# ethernet_ipphone_sch.net
KiCad netlist of a schematic drawn in Altium Designer
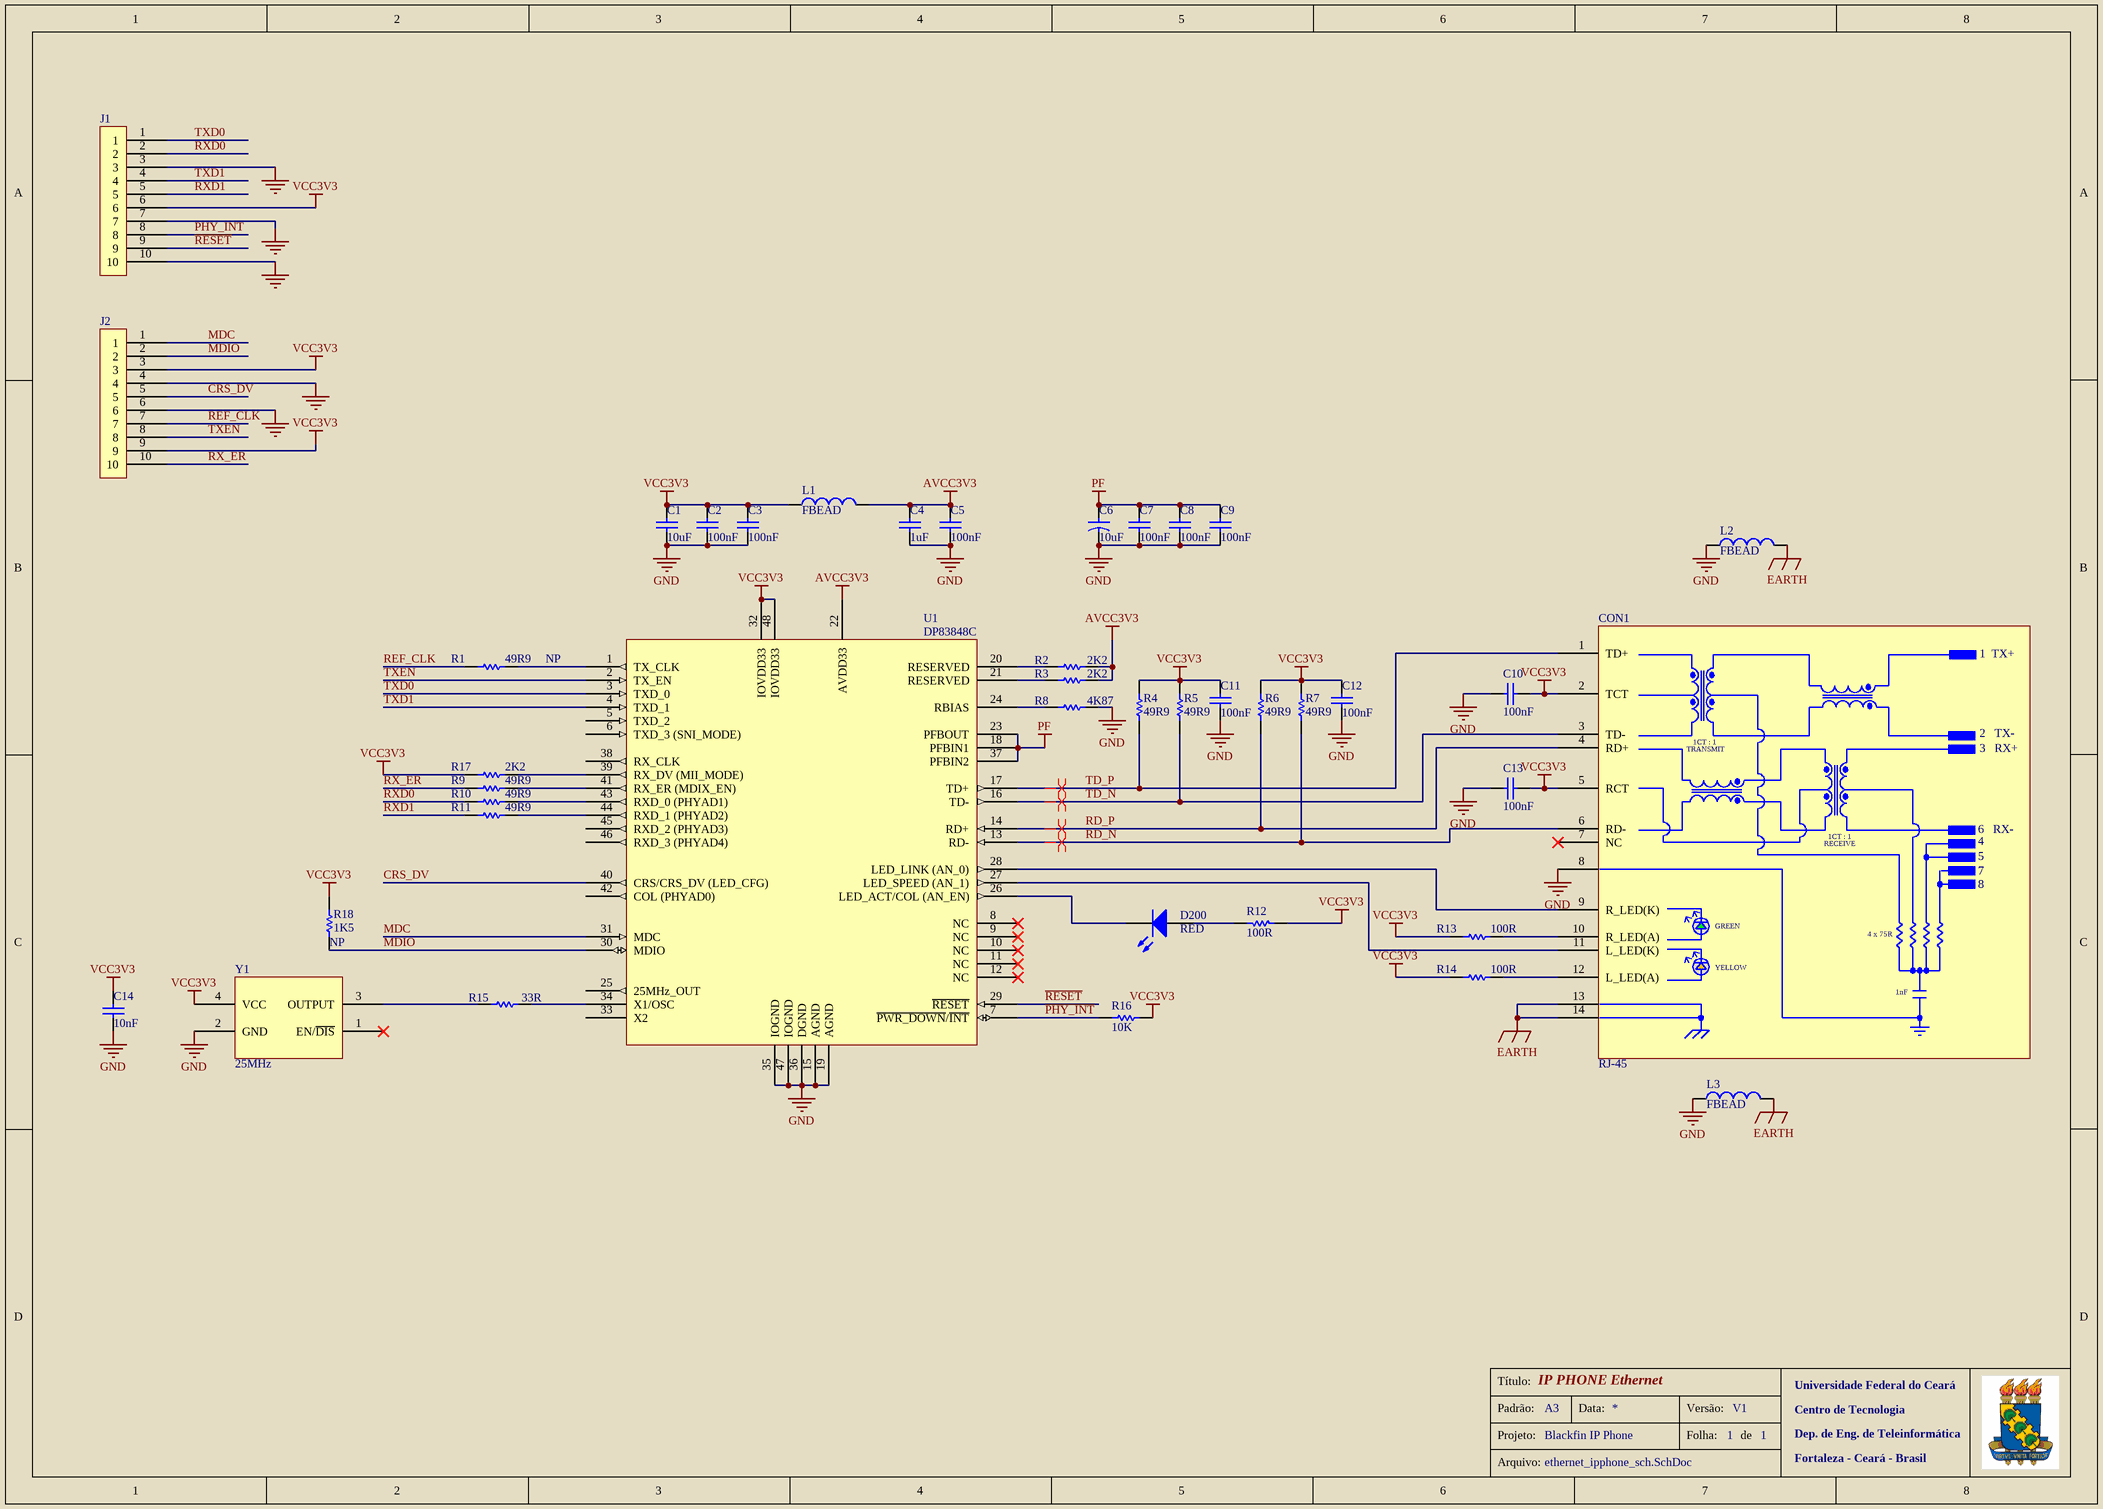
[diagram p0: ethernet_ipphone_sch.SchDoc]

(export (version "E")
  (design (tool "Eeschema 10.0.6"))
  (components
    (comp (ref "C1")
      (value "10uF")
      (footprint "ip_phone:CC2012-0805")
      (description "Capacitor SMD/SMT 0603 10uF 6.3volts X5R 20%")
      (fields (field (name "EVENDORPART#") "810-C2012Y5V1A106Z") (field (name "MANUFACTURER") "TDK"))
      (libsource (lib "ip_phone") (part "Capacitor"))
    )
    (comp (ref "C2")
      (value "100nF")
      (footprint "ip_phone:CC1005-0402")
      (description "MLCC - SMD/SMT 0.1UF 16V 10% 0402")
      (fields (field (name "EVENDORPART#") "810-C1005X7R1C104K") (field (name "MANUFACTURER") "TDK"))
      (libsource (lib "ip_phone") (part "Capacitor"))
    )
    (comp (ref "C3")
      (value "100nF")
      (footprint "ip_phone:CC1005-0402")
      (description "MLCC - SMD/SMT 0.1UF 16V 10% 0402")
      (fields (field (name "EVENDORPART#") "810-C1005X7R1C104K") (field (name "MANUFACTURER") "TDK"))
      (libsource (lib "ip_phone") (part "Capacitor"))
    )
    (comp (ref "C4")
      (value "1uF")
      (footprint "ip_phone:CC1608-0603")
      (description "Capacitor")
      (libsource (lib "ip_phone") (part "Capacitor"))
    )
    (comp (ref "C5")
      (value "100nF")
      (footprint "ip_phone:CC1005-0402")
      (description "MLCC - SMD/SMT 0.1UF 16V 10% 0402")
      (fields (field (name "EVENDORPART#") "810-C1005X7R1C104K") (field (name "MANUFACTURER") "TDK"))
      (libsource (lib "ip_phone") (part "Capacitor"))
    )
    (comp (ref "C6")
      (value "10uF")
      (footprint "ip_phone:C_Case_A")
      (description "Capacitor Tantalum")
      (libsource (lib "ip_phone") (part "Capacitor_Tan"))
    )
    (comp (ref "C7")
      (value "100nF")
      (footprint "ip_phone:CC1005-0402")
      (description "MLCC - SMD/SMT 0.1UF 16V 10% 0402")
      (fields (field (name "EVENDORPART#") "810-C1005X7R1C104K") (field (name "MANUFACTURER") "TDK"))
      (libsource (lib "ip_phone") (part "Capacitor"))
    )
    (comp (ref "C8")
      (value "100nF")
      (footprint "ip_phone:CC1005-0402")
      (description "MLCC - SMD/SMT 0.1UF 16V 10% 0402")
      (fields (field (name "EVENDORPART#") "810-C1005X7R1C104K") (field (name "MANUFACTURER") "TDK"))
      (libsource (lib "ip_phone") (part "Capacitor"))
    )
    (comp (ref "C9")
      (value "100nF")
      (footprint "ip_phone:CC1005-0402")
      (description "MLCC - SMD/SMT 0.1UF 16V 10% 0402")
      (fields (field (name "EVENDORPART#") "810-C1005X7R1C104K") (field (name "MANUFACTURER") "TDK"))
      (libsource (lib "ip_phone") (part "Capacitor"))
    )
    (comp (ref "C10")
      (value "100nF")
      (footprint "ip_phone:CC1005-0402")
      (description "MLCC - SMD/SMT 0.1UF 16V 10% 0402")
      (fields (field (name "EVENDORPART#") "810-C1005X7R1C104K") (field (name "MANUFACTURER") "TDK"))
      (libsource (lib "ip_phone") (part "Capacitor"))
    )
    (comp (ref "C11")
      (value "100nF")
      (footprint "ip_phone:CC1005-0402")
      (description "MLCC - SMD/SMT 0.1UF 16V 10% 0402")
      (fields (field (name "EVENDORPART#") "810-C1005X7R1C104K") (field (name "MANUFACTURER") "TDK"))
      (libsource (lib "ip_phone") (part "Capacitor"))
    )
    (comp (ref "C12")
      (value "100nF")
      (footprint "ip_phone:CC1005-0402")
      (description "MLCC - SMD/SMT 0.1UF 16V 10% 0402")
      (fields (field (name "EVENDORPART#") "810-C1005X7R1C104K") (field (name "MANUFACTURER") "TDK"))
      (libsource (lib "ip_phone") (part "Capacitor"))
    )
    (comp (ref "C13")
      (value "100nF")
      (footprint "ip_phone:CC1005-0402")
      (description "MLCC - SMD/SMT 0.1UF 16V 10% 0402")
      (fields (field (name "EVENDORPART#") "810-C1005X7R1C104K") (field (name "MANUFACTURER") "TDK"))
      (libsource (lib "ip_phone") (part "Capacitor"))
    )
    (comp (ref "C14")
      (value "10nF")
      (footprint "ip_phone:CC1005-0402")
      (description "Capacitor SMD/SMT 0402 0.01uF 16volts X7R 10%")
      (fields (field (name "EVENDORPART#") "810-C1005X7R1C103K") (field (name "MANUFACTURER") "TDK"))
      (libsource (lib "ip_phone") (part "Capacitor"))
    )
    (comp (ref "CON1")
      (value "RJ-45")
      (footprint "ip_phone:RJ-45")
      (description "Ethernet & Telecom Connectors 1X1 RJ45 JACK")
      (fields (field (name "EVENDORPART#") "673-J1012F01C") (field (name "PART#") "J1012F01C"))
      (libsource (lib "ip_phone") (part "RJ-45"))
    )
    (comp (ref "D200")
      (value "RED")
      (footprint "ip_phone:LED_0603")
      (description "LED")
      (fields (field (name "PART#") "APT1608SURCK") (field (name "MANUFACTURER") "Kingbright"))
      (libsource (lib "ip_phone") (part "LED"))
    )
    (comp (ref "J1")
      (value "CONN HEADER")
      (footprint "ip_phone:CONECTOR_10_PIN")
      (description "CONN HEADER .050\" 10POS PCB GOLD")
      (fields
        (field (name "EVENDORPART#") "S9014E-10-ND")
        (field (name "MANUFACTURER") "Sullins Connector Solutions")
      )
      (libsource (lib "ip_phone") (part "Conector 10pin"))
    )
    (comp (ref "J2")
      (value "CONN HEADER")
      (footprint "ip_phone:CONECTOR_10_PIN")
      (description "CONN HEADER .050\" 10POS PCB GOLD")
      (fields
        (field (name "EVENDORPART#") "S9014E-10-ND")
        (field (name "MANUFACTURER") "Sullins Connector Solutions")
      )
      (libsource (lib "ip_phone") (part "Conector 10pin"))
    )
    (comp (ref "L1")
      (value "FBEAD")
      (footprint "ip_phone:INDUTOR_0603")
      (description "Inductor")
      (libsource (lib "ip_phone") (part "Inductor"))
    )
    (comp (ref "L2")
      (value "FBEAD")
      (footprint "ip_phone:INDUTOR_0603")
      (description "Inductor")
      (libsource (lib "ip_phone") (part "Inductor"))
    )
    (comp (ref "L3")
      (value "FBEAD")
      (footprint "ip_phone:INDUTOR_0603")
      (description "Inductor")
      (libsource (lib "ip_phone") (part "Inductor"))
    )
    (comp (ref "R1")
      (value "49R9")
      (footprint "ip_phone:CR1005-0402_NP")
      (description "Thick Film Resistors - SMD 1/16watt 49.9ohms 1% 0402")
      (fields
        (field (name "EVENDORPART#") "71-CRCW0402-49.9-E3")
        (field (name "MANUFACTURER") "Vishay/Dale")
        (field (name "NP") "NP")
      )
      (libsource (lib "ip_phone") (part "Resistor"))
    )
    (comp (ref "R2")
      (value "2K2")
      (footprint "ip_phone:CR1005-0402")
      (description "Thick Film Resistors SMD 0402 2K2 5%  1/16 W")
      (fields (field (name "EVENDORPART#") "311-2.2KJRCT-ND") (field (name "MANUFACTURER") "Yageo"))
      (libsource (lib "ip_phone") (part "Resistor"))
    )
    (comp (ref "R3")
      (value "2K2")
      (footprint "ip_phone:CR1005-0402")
      (description "Thick Film Resistors SMD 0402 2K2 5%  1/16 W")
      (fields (field (name "EVENDORPART#") "311-2.2KJRCT-ND") (field (name "MANUFACTURER") "Yageo"))
      (libsource (lib "ip_phone") (part "Resistor"))
    )
    (comp (ref "R4")
      (value "49R9")
      (footprint "ip_phone:CR1005-0402")
      (description "Thick Film Resistors - SMD 1/16watt 49.9ohms 1% 0402")
      (fields (field (name "EVENDORPART#") "71-CRCW0402-49.9-E3") (field (name "MANUFACTURER") "Vishay/Dale"))
      (libsource (lib "ip_phone") (part "Resistor"))
    )
    (comp (ref "R5")
      (value "49R9")
      (footprint "ip_phone:CR1005-0402")
      (description "Thick Film Resistors - SMD 1/16watt 49.9ohms 1% 0402")
      (fields (field (name "EVENDORPART#") "71-CRCW0402-49.9-E3") (field (name "MANUFACTURER") "Vishay/Dale"))
      (libsource (lib "ip_phone") (part "Resistor"))
    )
    (comp (ref "R6")
      (value "49R9")
      (footprint "ip_phone:CR1005-0402")
      (description "Thick Film Resistors - SMD 1/16watt 49.9ohms 1% 0402")
      (fields (field (name "EVENDORPART#") "71-CRCW0402-49.9-E3") (field (name "MANUFACTURER") "Vishay/Dale"))
      (libsource (lib "ip_phone") (part "Resistor"))
    )
    (comp (ref "R7")
      (value "49R9")
      (footprint "ip_phone:CR1005-0402")
      (description "Thick Film Resistors - SMD 1/16watt 49.9ohms 1% 0402")
      (fields (field (name "EVENDORPART#") "71-CRCW0402-49.9-E3") (field (name "MANUFACTURER") "Vishay/Dale"))
      (libsource (lib "ip_phone") (part "Resistor"))
    )
    (comp (ref "R8")
      (value "4K87")
      (footprint "ip_phone:CR1608-0603")
      (libsource (lib "ip_phone") (part "Resistor"))
    )
    (comp (ref "R9")
      (value "49R9")
      (footprint "ip_phone:CR1005-0402")
      (description "Thick Film Resistors - SMD 1/16watt 49.9ohms 1% 0402")
      (fields (field (name "EVENDORPART#") "71-CRCW0402-49.9-E3") (field (name "MANUFACTURER") "Vishay/Dale"))
      (libsource (lib "ip_phone") (part "Resistor"))
    )
    (comp (ref "R10")
      (value "49R9")
      (footprint "ip_phone:CR1005-0402")
      (description "Thick Film Resistors - SMD 1/16watt 49.9ohms 1% 0402")
      (fields (field (name "EVENDORPART#") "71-CRCW0402-49.9-E3") (field (name "MANUFACTURER") "Vishay/Dale"))
      (libsource (lib "ip_phone") (part "Resistor"))
    )
    (comp (ref "R11")
      (value "49R9")
      (footprint "ip_phone:CR1005-0402")
      (description "Thick Film Resistors - SMD 1/16watt 49.9ohms 1% 0402")
      (fields (field (name "EVENDORPART#") "71-CRCW0402-49.9-E3") (field (name "MANUFACTURER") "Vishay/Dale"))
      (libsource (lib "ip_phone") (part "Resistor"))
    )
    (comp (ref "R12")
      (value "100R")
      (footprint "ip_phone:CR1608-0603")
      (description "Thick Film Resistors 1/16WATT 100R 0402")
      (fields (field (name "EVENDORPART#") "652-CR0603-JW-101GLF") (field (name "MANUFACTURER") "Bourns"))
      (libsource (lib "ip_phone") (part "Resistor"))
    )
    (comp (ref "R13")
      (value "100R")
      (footprint "ip_phone:CR1608-0603")
      (description "Thick Film Resistors 1/16WATT 100R 0402")
      (fields (field (name "EVENDORPART#") "652-CR0603-JW-101GLF") (field (name "MANUFACTURER") "Bourns"))
      (libsource (lib "ip_phone") (part "Resistor"))
    )
    (comp (ref "R14")
      (value "100R")
      (footprint "ip_phone:CR1608-0603")
      (description "Thick Film Resistors 1/16WATT 100R 0402")
      (fields (field (name "EVENDORPART#") "652-CR0603-JW-101GLF") (field (name "MANUFACTURER") "Bourns"))
      (libsource (lib "ip_phone") (part "Resistor"))
    )
    (comp (ref "R15")
      (value "33R")
      (footprint "ip_phone:CR1005-0402")
      (description "Thick Film Resistors SMD 0402 33R 5%  1/16 W")
      (fields (field (name "EVENDORPART#") "311-33JRCT-ND") (field (name "MANUFACTURER") "Yageo"))
      (libsource (lib "ip_phone") (part "Resistor"))
    )
    (comp (ref "R16")
      (value "10K")
      (footprint "ip_phone:CR1005-0402")
      (description "Thick Film Resistors SMD 0402 10K 5%  1/16 W")
      (fields (field (name "EVENDORPART#") "311-10KJRCT-ND") (field (name "MANUFACTURER") "Yageo"))
      (libsource (lib "ip_phone") (part "Resistor"))
    )
    (comp (ref "R17")
      (value "2K2")
      (footprint "ip_phone:CR1005-0402")
      (description "Thick Film Resistors SMD 0402 2K2 5%  1/16 W")
      (fields (field (name "EVENDORPART#") "311-2.2KJRCT-ND") (field (name "MANUFACTURER") "Yageo"))
      (libsource (lib "ip_phone") (part "Resistor"))
    )
    (comp (ref "R18")
      (value "1K5")
      (footprint "ip_phone:CR1608-0603")
      (description "Thick Film Resistors 1.5KOHM 5% 1/10W")
      (fields
        (field (name "EVENDORPART#") "52-CR0603-JW-152GLF")
        (field (name "MANUFACTURER") "Bourns")
        (field (name "NP") "NP")
      )
      (libsource (lib "ip_phone") (part "Resistor"))
    )
    (comp (ref "U1")
      (value "DP83848C")
      (footprint "ip_phone:LQFP48")
      (description "IC TXRX ETHERNET PHYTER 48-LQFP")
      (fields (field (name "MANUFACTURER") "National Semiconductor") (field (name "PART#") "DP83848CVV/NOPB"))
      (libsource (lib "ip_phone") (part "DP83848C"))
    )
    (comp (ref "Y1")
      (value "25MHz")
      (footprint "ip_phone:OSC_25MHz_PHY")
      (description "Standard Clock Oscillators 3.3V 25MHZ")
      (fields (field (name "EVENDORPART#") "815-ASV-25-EJ-T") (field (name "PART#") "ASV-25.000MHZ-EJ-T"))
      (libsource (lib "ip_phone") (part "Oscillator_25MHz_Phy"))
    )
  )
  (nets
    (net (code "1") (name "/CRS_DV") (class "Default")
      (node (ref "J2") (pin "5") (pinfunction "5_5") (pintype "passive"))
      (node (ref "U1") (pin "40") (pinfunction "CRS/CRS_DV_(LED_CFG)_40") (pintype "output"))
    )
    (net (code "2") (name "/MDC") (class "Default")
      (node (ref "J2") (pin "1") (pinfunction "1_1") (pintype "passive"))
      (node (ref "U1") (pin "31") (pinfunction "MDC_31") (pintype "input"))
    )
    (net (code "3") (name "/MDIO") (class "Default")
      (node (ref "J2") (pin "2") (pinfunction "2_2") (pintype "passive"))
      (node (ref "R18") (pin "2") (pinfunction "2_2") (pintype "passive"))
      (node (ref "U1") (pin "30") (pinfunction "MDIO_30") (pintype "bidirectional"))
    )
    (net (code "4") (name "/RD_N") (class "Default")
      (node (ref "CON1") (pin "6") (pinfunction "RD-_6") (pintype "passive"))
      (node (ref "R7") (pin "1") (pinfunction "1_1") (pintype "passive"))
      (node (ref "U1") (pin "13") (pinfunction "RD-_13") (pintype "input"))
    )
    (net (code "5") (name "/RD_P") (class "Default")
      (node (ref "CON1") (pin "4") (pinfunction "RD+_4") (pintype "passive"))
      (node (ref "R6") (pin "1") (pinfunction "1_1") (pintype "passive"))
      (node (ref "U1") (pin "14") (pinfunction "RD+_14") (pintype "input"))
    )
    (net (code "6") (name "/REF_CLK") (class "Default")
      (node (ref "J2") (pin "7") (pinfunction "7_7") (pintype "passive"))
      (node (ref "R1") (pin "1") (pinfunction "1_1") (pintype "passive"))
    )
    (net (code "7") (name "/RXD0") (class "Default")
      (node (ref "J1") (pin "2") (pinfunction "2_2") (pintype "passive"))
      (node (ref "R10") (pin "1") (pinfunction "1_1") (pintype "passive"))
    )
    (net (code "8") (name "/RXD1") (class "Default")
      (node (ref "J1") (pin "5") (pinfunction "5_5") (pintype "passive"))
      (node (ref "R11") (pin "1") (pinfunction "1_1") (pintype "passive"))
    )
    (net (code "9") (name "/RX_ER") (class "Default")
      (node (ref "J2") (pin "10") (pinfunction "10_10") (pintype "passive"))
      (node (ref "R9") (pin "1") (pinfunction "1_1") (pintype "passive"))
    )
    (net (code "10") (name "/TD_N") (class "Default")
      (node (ref "CON1") (pin "3") (pinfunction "TD-_3") (pintype "passive"))
      (node (ref "R5") (pin "1") (pinfunction "1_1") (pintype "passive"))
      (node (ref "U1") (pin "16") (pinfunction "TD-_16") (pintype "output"))
    )
    (net (code "11") (name "/TD_P") (class "Default")
      (node (ref "CON1") (pin "1") (pinfunction "TD+_1") (pintype "passive"))
      (node (ref "R4") (pin "1") (pinfunction "1_1") (pintype "passive"))
      (node (ref "U1") (pin "17") (pinfunction "TD+_17") (pintype "output"))
    )
    (net (code "12") (name "/TXD0") (class "Default")
      (node (ref "J1") (pin "1") (pinfunction "1_1") (pintype "passive"))
      (node (ref "U1") (pin "3") (pinfunction "TXD_0_3") (pintype "input"))
    )
    (net (code "13") (name "/TXD1") (class "Default")
      (node (ref "J1") (pin "4") (pinfunction "4_4") (pintype "passive"))
      (node (ref "U1") (pin "4") (pinfunction "TXD_1_4") (pintype "input"))
    )
    (net (code "14") (name "/TXEN") (class "Default")
      (node (ref "J2") (pin "8") (pinfunction "8_8") (pintype "passive"))
      (node (ref "U1") (pin "2") (pinfunction "TX_EN_2") (pintype "input"))
    )
    (net (code "15") (name "/~{PHY_INT}") (class "Default")
      (node (ref "J1") (pin "8") (pinfunction "8_8") (pintype "passive"))
      (node (ref "R16") (pin "2") (pinfunction "2_2") (pintype "passive"))
      (node (ref "U1") (pin "7") (pinfunction "~{PWR_DOWN}/~{INT}_7") (pintype "bidirectional"))
    )
    (net (code "16") (name "/~{RESET}") (class "Default")
      (node (ref "J1") (pin "9") (pinfunction "9_9") (pintype "passive"))
      (node (ref "U1") (pin "29") (pinfunction "~{RESET}_29") (pintype "input"))
    )
    (net (code "17") (name "AVCC3V3") (class "Default")
      (node (ref "C4") (pin "2") (pinfunction "2_2") (pintype "passive"))
      (node (ref "C5") (pin "2") (pinfunction "2_2") (pintype "passive"))
      (node (ref "L1") (pin "2") (pinfunction "2_2") (pintype "passive"))
      (node (ref "R2") (pin "2") (pinfunction "2_2") (pintype "passive"))
      (node (ref "R3") (pin "2") (pinfunction "2_2") (pintype "passive"))
      (node (ref "U1") (pin "22") (pinfunction "AVDD33_22") (pintype "power_in"))
    )
    (net (code "18") (name "EARTH") (class "Default")
      (node (ref "CON1") (pin "13") (pinfunction "GND_13") (pintype "passive"))
      (node (ref "CON1") (pin "14") (pinfunction "GND_14") (pintype "passive"))
      (node (ref "L2") (pin "2") (pinfunction "2_2") (pintype "passive"))
      (node (ref "L3") (pin "2") (pinfunction "2_2") (pintype "passive"))
    )
    (net (code "19") (name "GND") (class "Default")
      (node (ref "C1") (pin "1") (pinfunction "1_1") (pintype "passive"))
      (node (ref "C10") (pin "2") (pinfunction "2_2") (pintype "passive"))
      (node (ref "C11") (pin "1") (pinfunction "1_1") (pintype "passive"))
      (node (ref "C12") (pin "1") (pinfunction "1_1") (pintype "passive"))
      (node (ref "C13") (pin "2") (pinfunction "2_2") (pintype "passive"))
      (node (ref "C14") (pin "1") (pinfunction "1_1") (pintype "passive"))
      (node (ref "C2") (pin "1") (pinfunction "1_1") (pintype "passive"))
      (node (ref "C3") (pin "1") (pinfunction "1_1") (pintype "passive"))
      (node (ref "C4") (pin "1") (pinfunction "1_1") (pintype "passive"))
      (node (ref "C5") (pin "1") (pinfunction "1_1") (pintype "passive"))
      (node (ref "C6") (pin "2") (pinfunction "2_2") (pintype "passive"))
      (node (ref "C7") (pin "1") (pinfunction "1_1") (pintype "passive"))
      (node (ref "C8") (pin "1") (pinfunction "1_1") (pintype "passive"))
      (node (ref "C9") (pin "1") (pinfunction "1_1") (pintype "passive"))
      (node (ref "CON1") (pin "8") (pinfunction "GND_8") (pintype "passive"))
      (node (ref "J1") (pin "10") (pinfunction "10_10") (pintype "passive"))
      (node (ref "J1") (pin "3") (pinfunction "3_3") (pintype "passive"))
      (node (ref "J1") (pin "7") (pinfunction "7_7") (pintype "passive"))
      (node (ref "J2") (pin "4") (pinfunction "4_4") (pintype "passive"))
      (node (ref "J2") (pin "6") (pinfunction "6_6") (pintype "passive"))
      (node (ref "L2") (pin "1") (pinfunction "1_1") (pintype "passive"))
      (node (ref "L3") (pin "1") (pinfunction "1_1") (pintype "passive"))
      (node (ref "R8") (pin "2") (pinfunction "2_2") (pintype "passive"))
      (node (ref "U1") (pin "15") (pinfunction "AGND_15") (pintype "power_in"))
      (node (ref "U1") (pin "19") (pinfunction "AGND_19") (pintype "power_in"))
      (node (ref "U1") (pin "35") (pinfunction "IOGND_35") (pintype "power_in"))
      (node (ref "U1") (pin "36") (pinfunction "DGND_36") (pintype "power_in"))
      (node (ref "U1") (pin "47") (pinfunction "IOGND_47") (pintype "power_in"))
      (node (ref "Y1") (pin "2") (pinfunction "GND_2") (pintype "passive"))
    )
    (net (code "20") (name "Net-(CON1-L_LED(A))") (class "Default")
      (node (ref "CON1") (pin "12") (pinfunction "L_LED(A)_12") (pintype "passive"))
      (node (ref "R14") (pin "1") (pinfunction "1_1") (pintype "passive"))
    )
    (net (code "21") (name "Net-(CON1-L_LED(K))") (class "Default")
      (node (ref "CON1") (pin "11") (pinfunction "L_LED(K)_11") (pintype "passive"))
      (node (ref "U1") (pin "27") (pinfunction "LED_SPEED_(AN_1)_27") (pintype "output"))
    )
    (net (code "22") (name "Net-(CON1-R_LED(A))") (class "Default")
      (node (ref "CON1") (pin "10") (pinfunction "R_LED(A)_10") (pintype "passive"))
      (node (ref "R13") (pin "1") (pinfunction "1_1") (pintype "passive"))
    )
    (net (code "23") (name "Net-(CON1-R_LED(K))") (class "Default")
      (node (ref "CON1") (pin "9") (pinfunction "R_LED(K)_9") (pintype "passive"))
      (node (ref "U1") (pin "28") (pinfunction "LED_LINK_(AN_0)_28") (pintype "output"))
    )
    (net (code "24") (name "Net-(D200-A)") (class "Default")
      (node (ref "D200") (pin "1") (pinfunction "A_1") (pintype "passive"))
      (node (ref "R12") (pin "1") (pinfunction "1_1") (pintype "passive"))
    )
    (net (code "25") (name "Net-(D200-K)") (class "Default")
      (node (ref "D200") (pin "2") (pinfunction "K_2") (pintype "passive"))
      (node (ref "U1") (pin "26") (pinfunction "LED_ACT/COL_(AN_EN)_26") (pintype "output"))
    )
    (net (code "26") (name "Net-(R2-Pad1)") (class "Default")
      (node (ref "R2") (pin "1") (pinfunction "1_1") (pintype "passive"))
      (node (ref "U1") (pin "20") (pinfunction "RESERVED_20") (pintype "passive"))
    )
    (net (code "27") (name "Net-(R3-Pad1)") (class "Default")
      (node (ref "R3") (pin "1") (pinfunction "1_1") (pintype "passive"))
      (node (ref "U1") (pin "21") (pinfunction "RESERVED_21") (pintype "passive"))
    )
    (net (code "28") (name "Net-(U1-RBIAS)") (class "Default")
      (node (ref "R8") (pin "1") (pinfunction "1_1") (pintype "passive"))
      (node (ref "U1") (pin "24") (pinfunction "RBIAS_24") (pintype "passive"))
    )
    (net (code "29") (name "Net-(U1-RXD_0_(PHYAD1))") (class "Default")
      (node (ref "R10") (pin "2") (pinfunction "2_2") (pintype "passive"))
      (node (ref "U1") (pin "43") (pinfunction "RXD_0_(PHYAD1)_43") (pintype "output"))
    )
    (net (code "30") (name "Net-(U1-RXD_1_(PHYAD2))") (class "Default")
      (node (ref "R11") (pin "2") (pinfunction "2_2") (pintype "passive"))
      (node (ref "U1") (pin "44") (pinfunction "RXD_1_(PHYAD2)_44") (pintype "output"))
    )
    (net (code "31") (name "Net-(U1-RX_DV_(MII_MODE))") (class "Default")
      (node (ref "R17") (pin "1") (pinfunction "1_1") (pintype "passive"))
      (node (ref "U1") (pin "39") (pinfunction "RX_DV_(MII_MODE)_39") (pintype "output"))
    )
    (net (code "32") (name "Net-(U1-RX_ER_(MDIX_EN))") (class "Default")
      (node (ref "R9") (pin "2") (pinfunction "2_2") (pintype "passive"))
      (node (ref "U1") (pin "41") (pinfunction "RX_ER_(MDIX_EN)_41") (pintype "output"))
    )
    (net (code "33") (name "Net-(U1-TX_CLK)") (class "Default")
      (node (ref "R1") (pin "2") (pinfunction "2_2") (pintype "passive"))
      (node (ref "U1") (pin "1") (pinfunction "TX_CLK_1") (pintype "output"))
    )
    (net (code "34") (name "Net-(U1-X1{slash}OSC)") (class "Default")
      (node (ref "R15") (pin "2") (pinfunction "2_2") (pintype "passive"))
      (node (ref "U1") (pin "34") (pinfunction "X1/OSC_34") (pintype "passive"))
    )
    (net (code "35") (name "Net-(Y1-OUTPUT)") (class "Default")
      (node (ref "R15") (pin "1") (pinfunction "1_1") (pintype "passive"))
      (node (ref "Y1") (pin "3") (pinfunction "OUTPUT_3") (pintype "passive"))
    )
    (net (code "36") (name "PF") (class "Default")
      (node (ref "C6") (pin "1") (pinfunction "1_1") (pintype "passive"))
      (node (ref "C7") (pin "2") (pinfunction "2_2") (pintype "passive"))
      (node (ref "C8") (pin "2") (pinfunction "2_2") (pintype "passive"))
      (node (ref "C9") (pin "2") (pinfunction "2_2") (pintype "passive"))
      (node (ref "U1") (pin "18") (pinfunction "PFBIN1_18") (pintype "passive"))
      (node (ref "U1") (pin "23") (pinfunction "PFBOUT_23") (pintype "passive"))
      (node (ref "U1") (pin "37") (pinfunction "PFBIN2_37") (pintype "passive"))
    )
    (net (code "37") (name "VCC3V3") (class "Default")
      (node (ref "C1") (pin "2") (pinfunction "2_2") (pintype "passive"))
      (node (ref "C10") (pin "1") (pinfunction "1_1") (pintype "passive"))
      (node (ref "C11") (pin "2") (pinfunction "2_2") (pintype "passive"))
      (node (ref "C12") (pin "2") (pinfunction "2_2") (pintype "passive"))
      (node (ref "C13") (pin "1") (pinfunction "1_1") (pintype "passive"))
      (node (ref "C14") (pin "2") (pinfunction "2_2") (pintype "passive"))
      (node (ref "C2") (pin "2") (pinfunction "2_2") (pintype "passive"))
      (node (ref "C3") (pin "2") (pinfunction "2_2") (pintype "passive"))
      (node (ref "CON1") (pin "2") (pinfunction "TCT_2") (pintype "passive"))
      (node (ref "CON1") (pin "5") (pinfunction "RCT_5") (pintype "passive"))
      (node (ref "J1") (pin "6") (pinfunction "6_6") (pintype "passive"))
      (node (ref "J2") (pin "3") (pinfunction "3_3") (pintype "passive"))
      (node (ref "J2") (pin "9") (pinfunction "9_9") (pintype "passive"))
      (node (ref "L1") (pin "1") (pinfunction "1_1") (pintype "passive"))
      (node (ref "R12") (pin "2") (pinfunction "2_2") (pintype "passive"))
      (node (ref "R13") (pin "2") (pinfunction "2_2") (pintype "passive"))
      (node (ref "R14") (pin "2") (pinfunction "2_2") (pintype "passive"))
      (node (ref "R16") (pin "1") (pinfunction "1_1") (pintype "passive"))
      (node (ref "R17") (pin "2") (pinfunction "2_2") (pintype "passive"))
      (node (ref "R18") (pin "1") (pinfunction "1_1") (pintype "passive"))
      (node (ref "R4") (pin "2") (pinfunction "2_2") (pintype "passive"))
      (node (ref "R5") (pin "2") (pinfunction "2_2") (pintype "passive"))
      (node (ref "R6") (pin "2") (pinfunction "2_2") (pintype "passive"))
      (node (ref "R7") (pin "2") (pinfunction "2_2") (pintype "passive"))
      (node (ref "U1") (pin "32") (pinfunction "IOVDD33_32") (pintype "power_in"))
      (node (ref "U1") (pin "48") (pinfunction "IOVDD33_48") (pintype "power_in"))
      (node (ref "Y1") (pin "4") (pinfunction "VCC_4") (pintype "passive"))
    )
    (net (code "38") (name "unconnected-(CON1-NC-Pad7)") (class "Default")
      (node (ref "CON1") (pin "7") (pinfunction "NC_7") (pintype "passive+no_connect"))
    )
    (net (code "39") (name "unconnected-(U1-25MHz_OUT-Pad25)") (class "Default")
      (node (ref "U1") (pin "25") (pinfunction "25MHz_OUT_25") (pintype "output"))
    )
    (net (code "40") (name "unconnected-(U1-COL_(PHYAD0)-Pad42)") (class "Default")
      (node (ref "U1") (pin "42") (pinfunction "COL_(PHYAD0)_42") (pintype "output"))
    )
    (net (code "41") (name "unconnected-(U1-NC-Pad8)") (class "Default")
      (node (ref "U1") (pin "8") (pinfunction "NC_8") (pintype "passive+no_connect"))
    )
    (net (code "42") (name "unconnected-(U1-NC-Pad9)") (class "Default")
      (node (ref "U1") (pin "9") (pinfunction "NC_9") (pintype "passive+no_connect"))
    )
    (net (code "43") (name "unconnected-(U1-NC-Pad10)") (class "Default")
      (node (ref "U1") (pin "10") (pinfunction "NC_10") (pintype "passive+no_connect"))
    )
    (net (code "44") (name "unconnected-(U1-NC-Pad11)") (class "Default")
      (node (ref "U1") (pin "11") (pinfunction "NC_11") (pintype "passive+no_connect"))
    )
    (net (code "45") (name "unconnected-(U1-NC-Pad12)") (class "Default")
      (node (ref "U1") (pin "12") (pinfunction "NC_12") (pintype "passive+no_connect"))
    )
    (net (code "46") (name "unconnected-(U1-RXD_2_(PHYAD3)-Pad45)") (class "Default")
      (node (ref "U1") (pin "45") (pinfunction "RXD_2_(PHYAD3)_45") (pintype "output"))
    )
    (net (code "47") (name "unconnected-(U1-RXD_3_(PHYAD4)-Pad46)") (class "Default")
      (node (ref "U1") (pin "46") (pinfunction "RXD_3_(PHYAD4)_46") (pintype "output"))
    )
    (net (code "48") (name "unconnected-(U1-RX_CLK-Pad38)") (class "Default")
      (node (ref "U1") (pin "38") (pinfunction "RX_CLK_38") (pintype "output"))
    )
    (net (code "49") (name "unconnected-(U1-TXD_2-Pad5)") (class "Default")
      (node (ref "U1") (pin "5") (pinfunction "TXD_2_5") (pintype "input"))
    )
    (net (code "50") (name "unconnected-(U1-TXD_3_(SNI_MODE)-Pad6)") (class "Default")
      (node (ref "U1") (pin "6") (pinfunction "TXD_3_(SNI_MODE)_6") (pintype "input"))
    )
    (net (code "51") (name "unconnected-(U1-X2-Pad33)") (class "Default")
      (node (ref "U1") (pin "33") (pinfunction "X2_33") (pintype "passive"))
    )
    (net (code "52") (name "unconnected-(Y1-EN{slash}~{DIS}-Pad1)") (class "Default")
      (node (ref "Y1") (pin "1") (pinfunction "EN/~{DIS}_1") (pintype "passive+no_connect"))
    )
  )
)
